# MCU_LF.net
KiCad netlist of a schematic drawn in Altium Designer
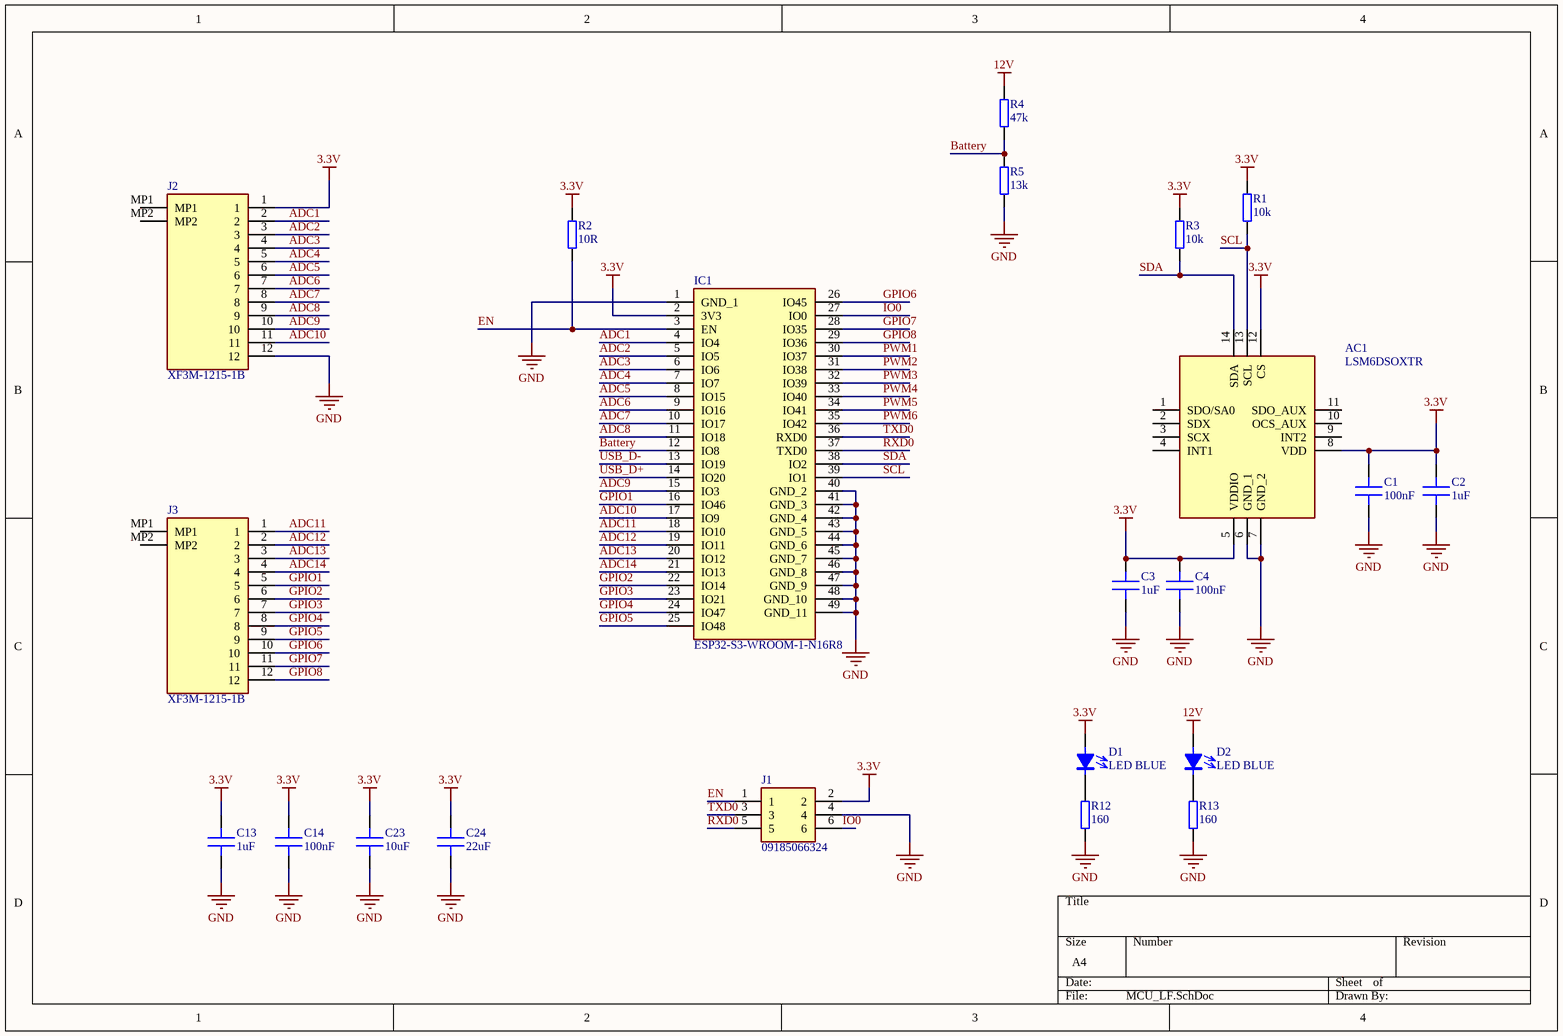
[diagram p0: MCU_LF.SchDoc]

(export (version "E")
  (design (tool "Eeschema 10.0.6"))
  (components
    (comp (ref "AC1")
      (value "LSM6DSOXTR")
      (footprint "SamacSys:LGA-14_1")
      (description "Accelerometer")
      (fields (field (name "MOUSER PART NUMBER") "511-LSM6DSOXTR"))
      (libsource (lib "lf_esp_sch_lib") (part "LSM6DSOXTR"))
    )
    (comp (ref "C1")
      (value "100nF")
      (footprint "C 0402")
      (description "MLCC Capacitor")
      (libsource (lib "Components") (part "Capacitor"))
    )
    (comp (ref "C2")
      (value "1uF")
      (footprint "C 0402")
      (description "MLCC Capacitor")
      (libsource (lib "Components") (part "Capacitor"))
    )
    (comp (ref "C3")
      (value "1uF")
      (footprint "C 0402")
      (description "MLCC Capacitor")
      (libsource (lib "Components") (part "Capacitor"))
    )
    (comp (ref "C4")
      (value "100nF")
      (footprint "C 0402")
      (description "MLCC Capacitor")
      (libsource (lib "Components") (part "Capacitor"))
    )
    (comp (ref "C13")
      (value "1uF")
      (footprint "C 0402")
      (description "MLCC Capacitor")
      (libsource (lib "Components") (part "Capacitor"))
    )
    (comp (ref "C14")
      (value "100nF")
      (footprint "C 0402")
      (description "MLCC Capacitor")
      (libsource (lib "Components") (part "Capacitor"))
    )
    (comp (ref "C23")
      (value "10uF")
      (footprint "C 0402")
      (description "MLCC Capacitor")
      (libsource (lib "Components") (part "Capacitor"))
    )
    (comp (ref "C24")
      (value "22uF")
      (footprint "C 0402")
      (description "MLCC Capacitor")
      (libsource (lib "Components") (part "Capacitor"))
    )
    (comp (ref "D1")
      (value "LED BLUE")
      (footprint "LED 0603 BLUE")
      (libsource (lib "Components") (part "LED BLUE"))
    )
    (comp (ref "D2")
      (value "LED BLUE")
      (footprint "LED 0603 BLUE")
      (libsource (lib "Components") (part "LED BLUE"))
    )
    (comp (ref "IC1")
      (value "ESP32-S3-WROOM-1-N16R8")
      (footprint "lf_esp_pcb_lib:ESP32S3WROOM1N16R8")
      (description "Integrated Circuit")
      (fields (field (name "MOUSER PART NUMBER") "356-ESP32S3WRM1N16R8"))
      (libsource (lib "lf_esp_sch_lib") (part "ESP32-S3-WROOM-1-N16R8"))
    )
    (comp (ref "J1")
      (value "09185066324")
      (footprint "SamacSys:09185066324")
      (description "Connector")
      (fields (field (name "MOUSER PART NUMBER") "617-09185066324"))
      (libsource (lib "lf_esp_sch_lib") (part "09185066324"))
    )
    (comp (ref "J2")
      (value "XF3M-1215-1B")
      (footprint "SamacSys:XF3M12151B")
      (description "Connector")
      (fields (field (name "MOUSER PART NUMBER") "653-XF3M-1215-1B"))
      (libsource (lib "lf_esp_sch_lib") (part "XF3M-1215-1B"))
    )
    (comp (ref "J3")
      (value "XF3M-1215-1B")
      (footprint "SamacSys:XF3M12151B")
      (description "Connector")
      (fields (field (name "MOUSER PART NUMBER") "653-XF3M-1215-1B"))
      (libsource (lib "lf_esp_sch_lib") (part "XF3M-1215-1B"))
    )
    (comp (ref "R1")
      (value "10k")
      (footprint "R 0402")
      (description "General pourpouse resistor")
      (libsource (lib "Components") (part "Resistor"))
    )
    (comp (ref "R2")
      (value "10R")
      (footprint "R 0402")
      (description "General pourpouse resistor")
      (libsource (lib "Components") (part "Resistor"))
    )
    (comp (ref "R3")
      (value "10k")
      (footprint "R 0402")
      (description "General pourpouse resistor")
      (libsource (lib "Components") (part "Resistor"))
    )
    (comp (ref "R4")
      (value "47k")
      (footprint "R 0402")
      (description "General pourpouse resistor")
      (libsource (lib "Components") (part "Resistor"))
    )
    (comp (ref "R5")
      (value "13k")
      (footprint "R 0402")
      (description "General pourpouse resistor")
      (libsource (lib "Components") (part "Resistor"))
    )
    (comp (ref "R12")
      (value "160")
      (footprint "R 0402")
      (description "General pourpouse resistor")
      (libsource (lib "Components") (part "Resistor"))
    )
    (comp (ref "R13")
      (value "160")
      (footprint "R 0402")
      (description "General pourpouse resistor")
      (libsource (lib "Components") (part "Resistor"))
    )
  )
  (nets
    (net (code "1") (name "/ADC1") (class "Default")
      (node (ref "IC1") (pin "4") (pinfunction "IO4_4") (pintype "passive"))
      (node (ref "J2") (pin "2") (pinfunction "2_2") (pintype "passive"))
    )
    (net (code "2") (name "/ADC2") (class "Default")
      (node (ref "IC1") (pin "5") (pinfunction "IO5_5") (pintype "passive"))
      (node (ref "J2") (pin "3") (pinfunction "3_3") (pintype "passive"))
    )
    (net (code "3") (name "/ADC3") (class "Default")
      (node (ref "IC1") (pin "6") (pinfunction "IO6_6") (pintype "passive"))
      (node (ref "J2") (pin "4") (pinfunction "4_4") (pintype "passive"))
    )
    (net (code "4") (name "/ADC4") (class "Default")
      (node (ref "IC1") (pin "7") (pinfunction "IO7_7") (pintype "passive"))
      (node (ref "J2") (pin "5") (pinfunction "5_5") (pintype "passive"))
    )
    (net (code "5") (name "/ADC5") (class "Default")
      (node (ref "IC1") (pin "8") (pinfunction "IO15_8") (pintype "passive"))
      (node (ref "J2") (pin "6") (pinfunction "6_6") (pintype "passive"))
    )
    (net (code "6") (name "/ADC6") (class "Default")
      (node (ref "IC1") (pin "9") (pinfunction "IO16_9") (pintype "passive"))
      (node (ref "J2") (pin "7") (pinfunction "7_7") (pintype "passive"))
    )
    (net (code "7") (name "/ADC7") (class "Default")
      (node (ref "IC1") (pin "10") (pinfunction "IO17_10") (pintype "passive"))
      (node (ref "J2") (pin "8") (pinfunction "8_8") (pintype "passive"))
    )
    (net (code "8") (name "/ADC8") (class "Default")
      (node (ref "IC1") (pin "11") (pinfunction "IO18_11") (pintype "passive"))
      (node (ref "J2") (pin "9") (pinfunction "9_9") (pintype "passive"))
    )
    (net (code "9") (name "/ADC9") (class "Default")
      (node (ref "IC1") (pin "15") (pinfunction "IO3_15") (pintype "passive"))
      (node (ref "J2") (pin "10") (pinfunction "10_10") (pintype "passive"))
    )
    (net (code "10") (name "/ADC10") (class "Default")
      (node (ref "IC1") (pin "17") (pinfunction "IO9_17") (pintype "passive"))
      (node (ref "J2") (pin "11") (pinfunction "11_11") (pintype "passive"))
    )
    (net (code "11") (name "/ADC11") (class "Default")
      (node (ref "IC1") (pin "18") (pinfunction "IO10_18") (pintype "passive"))
      (node (ref "J3") (pin "1") (pinfunction "1_1") (pintype "passive"))
    )
    (net (code "12") (name "/ADC12") (class "Default")
      (node (ref "IC1") (pin "19") (pinfunction "IO11_19") (pintype "passive"))
      (node (ref "J3") (pin "2") (pinfunction "2_2") (pintype "passive"))
    )
    (net (code "13") (name "/ADC13") (class "Default")
      (node (ref "IC1") (pin "20") (pinfunction "IO12_20") (pintype "passive"))
      (node (ref "J3") (pin "3") (pinfunction "3_3") (pintype "passive"))
    )
    (net (code "14") (name "/ADC14") (class "Default")
      (node (ref "IC1") (pin "21") (pinfunction "IO13_21") (pintype "passive"))
      (node (ref "J3") (pin "4") (pinfunction "4_4") (pintype "passive"))
    )
    (net (code "15") (name "/Battery") (class "Default")
      (node (ref "IC1") (pin "12") (pinfunction "IO8_12") (pintype "passive"))
      (node (ref "R4") (pin "1") (pinfunction "1_1") (pintype "passive"))
      (node (ref "R5") (pin "2") (pinfunction "2_2") (pintype "passive"))
    )
    (net (code "16") (name "/EN") (class "Default")
      (node (ref "IC1") (pin "3") (pinfunction "EN_3") (pintype "passive"))
      (node (ref "J1") (pin "1") (pinfunction "1_1") (pintype "passive"))
      (node (ref "R2") (pin "1") (pinfunction "1_1") (pintype "passive"))
    )
    (net (code "17") (name "/GPIO1") (class "Default")
      (node (ref "IC1") (pin "16") (pinfunction "IO46_16") (pintype "passive"))
      (node (ref "J3") (pin "5") (pinfunction "5_5") (pintype "passive"))
    )
    (net (code "18") (name "/GPIO2") (class "Default")
      (node (ref "IC1") (pin "22") (pinfunction "IO14_22") (pintype "passive"))
      (node (ref "J3") (pin "6") (pinfunction "6_6") (pintype "passive"))
    )
    (net (code "19") (name "/GPIO3") (class "Default")
      (node (ref "IC1") (pin "23") (pinfunction "IO21_23") (pintype "passive"))
      (node (ref "J3") (pin "7") (pinfunction "7_7") (pintype "passive"))
    )
    (net (code "20") (name "/GPIO4") (class "Default")
      (node (ref "IC1") (pin "24") (pinfunction "IO47_24") (pintype "passive"))
      (node (ref "J3") (pin "8") (pinfunction "8_8") (pintype "passive"))
    )
    (net (code "21") (name "/GPIO5") (class "Default")
      (node (ref "IC1") (pin "25") (pinfunction "IO48_25") (pintype "passive"))
      (node (ref "J3") (pin "9") (pinfunction "9_9") (pintype "passive"))
    )
    (net (code "22") (name "/GPIO6") (class "Default")
      (node (ref "IC1") (pin "26") (pinfunction "IO45_26") (pintype "passive"))
      (node (ref "J3") (pin "10") (pinfunction "10_10") (pintype "passive"))
    )
    (net (code "23") (name "/GPIO7") (class "Default")
      (node (ref "IC1") (pin "28") (pinfunction "IO35_28") (pintype "passive"))
      (node (ref "J3") (pin "11") (pinfunction "11_11") (pintype "passive"))
    )
    (net (code "24") (name "/GPIO8") (class "Default")
      (node (ref "IC1") (pin "29") (pinfunction "IO36_29") (pintype "passive"))
      (node (ref "J3") (pin "12") (pinfunction "12_12") (pintype "passive"))
    )
    (net (code "25") (name "/IO0") (class "Default")
      (node (ref "IC1") (pin "27") (pinfunction "IO0_27") (pintype "passive"))
      (node (ref "J1") (pin "6") (pinfunction "6_6") (pintype "passive"))
    )
    (net (code "26") (name "/PWM1") (class "Default")
      (node (ref "IC1") (pin "30") (pinfunction "IO37_30") (pintype "passive"))
    )
    (net (code "27") (name "/PWM2") (class "Default")
      (node (ref "IC1") (pin "31") (pinfunction "IO38_31") (pintype "passive"))
    )
    (net (code "28") (name "/PWM3") (class "Default")
      (node (ref "IC1") (pin "32") (pinfunction "IO39_32") (pintype "passive"))
    )
    (net (code "29") (name "/PWM4") (class "Default")
      (node (ref "IC1") (pin "33") (pinfunction "IO40_33") (pintype "passive"))
    )
    (net (code "30") (name "/PWM5") (class "Default")
      (node (ref "IC1") (pin "34") (pinfunction "IO41_34") (pintype "passive"))
    )
    (net (code "31") (name "/PWM6") (class "Default")
      (node (ref "IC1") (pin "35") (pinfunction "IO42_35") (pintype "passive"))
    )
    (net (code "32") (name "/RXD0") (class "Default")
      (node (ref "IC1") (pin "37") (pinfunction "TXD0_37") (pintype "passive"))
      (node (ref "J1") (pin "5") (pinfunction "5_5") (pintype "passive"))
    )
    (net (code "33") (name "/SCL") (class "Default")
      (node (ref "AC1") (pin "13") (pinfunction "SCL_13") (pintype "passive"))
      (node (ref "IC1") (pin "39") (pinfunction "IO1_39") (pintype "passive"))
      (node (ref "R1") (pin "1") (pinfunction "1_1") (pintype "passive"))
    )
    (net (code "34") (name "/SDA") (class "Default")
      (node (ref "AC1") (pin "14") (pinfunction "SDA_14") (pintype "passive"))
      (node (ref "IC1") (pin "38") (pinfunction "IO2_38") (pintype "passive"))
      (node (ref "R3") (pin "1") (pinfunction "1_1") (pintype "passive"))
    )
    (net (code "35") (name "/TXD0") (class "Default")
      (node (ref "IC1") (pin "36") (pinfunction "RXD0_36") (pintype "passive"))
      (node (ref "J1") (pin "3") (pinfunction "3_3") (pintype "passive"))
    )
    (net (code "36") (name "/USB_D+") (class "Default")
      (node (ref "IC1") (pin "14") (pinfunction "IO20_14") (pintype "passive"))
    )
    (net (code "37") (name "/USB_D-") (class "Default")
      (node (ref "IC1") (pin "13") (pinfunction "IO19_13") (pintype "passive"))
    )
    (net (code "38") (name "3.3V") (class "Default")
      (node (ref "AC1") (pin "12") (pinfunction "CS_12") (pintype "passive"))
      (node (ref "AC1") (pin "5") (pinfunction "VDDIO_5") (pintype "passive"))
      (node (ref "AC1") (pin "8") (pinfunction "VDD_8") (pintype "passive"))
      (node (ref "C1") (pin "1") (pinfunction "1_1") (pintype "passive"))
      (node (ref "C13") (pin "1") (pinfunction "1_1") (pintype "passive"))
      (node (ref "C14") (pin "1") (pinfunction "1_1") (pintype "passive"))
      (node (ref "C2") (pin "1") (pinfunction "1_1") (pintype "passive"))
      (node (ref "C23") (pin "1") (pinfunction "1_1") (pintype "passive"))
      (node (ref "C24") (pin "1") (pinfunction "1_1") (pintype "passive"))
      (node (ref "C3") (pin "1") (pinfunction "1_1") (pintype "passive"))
      (node (ref "C4") (pin "1") (pinfunction "1_1") (pintype "passive"))
      (node (ref "D1") (pin "1") (pinfunction "1_1") (pintype "passive"))
      (node (ref "IC1") (pin "2") (pinfunction "3V3_2") (pintype "passive"))
      (node (ref "J1") (pin "2") (pinfunction "2_2") (pintype "passive"))
      (node (ref "J2") (pin "1") (pinfunction "1_1") (pintype "passive"))
      (node (ref "R1") (pin "2") (pinfunction "2_2") (pintype "passive"))
      (node (ref "R2") (pin "2") (pinfunction "2_2") (pintype "passive"))
      (node (ref "R3") (pin "2") (pinfunction "2_2") (pintype "passive"))
    )
    (net (code "39") (name "12V") (class "Default")
      (node (ref "D2") (pin "1") (pinfunction "1_1") (pintype "passive"))
      (node (ref "R4") (pin "2") (pinfunction "2_2") (pintype "passive"))
    )
    (net (code "40") (name "GND") (class "Default")
      (node (ref "AC1") (pin "6") (pinfunction "GND_1_6") (pintype "passive"))
      (node (ref "AC1") (pin "7") (pinfunction "GND_2_7") (pintype "passive"))
      (node (ref "C1") (pin "2") (pinfunction "2_2") (pintype "passive"))
      (node (ref "C13") (pin "2") (pinfunction "2_2") (pintype "passive"))
      (node (ref "C14") (pin "2") (pinfunction "2_2") (pintype "passive"))
      (node (ref "C2") (pin "2") (pinfunction "2_2") (pintype "passive"))
      (node (ref "C23") (pin "2") (pinfunction "2_2") (pintype "passive"))
      (node (ref "C24") (pin "2") (pinfunction "2_2") (pintype "passive"))
      (node (ref "C3") (pin "2") (pinfunction "2_2") (pintype "passive"))
      (node (ref "C4") (pin "2") (pinfunction "2_2") (pintype "passive"))
      (node (ref "IC1") (pin "1") (pinfunction "GND_1_1") (pintype "passive"))
      (node (ref "IC1") (pin "40") (pinfunction "GND_2_40") (pintype "passive"))
      (node (ref "IC1") (pin "41") (pinfunction "GND_3_41") (pintype "passive"))
      (node (ref "IC1") (pin "42") (pinfunction "GND_4_42") (pintype "passive"))
      (node (ref "IC1") (pin "43") (pinfunction "GND_5_43") (pintype "passive"))
      (node (ref "IC1") (pin "44") (pinfunction "GND_6_44") (pintype "passive"))
      (node (ref "IC1") (pin "45") (pinfunction "GND_7_45") (pintype "passive"))
      (node (ref "IC1") (pin "46") (pinfunction "GND_8_46") (pintype "passive"))
      (node (ref "IC1") (pin "47") (pinfunction "GND_9_47") (pintype "passive"))
      (node (ref "IC1") (pin "48") (pinfunction "GND_10_48") (pintype "passive"))
      (node (ref "IC1") (pin "49") (pinfunction "GND_11_49") (pintype "passive"))
      (node (ref "J1") (pin "4") (pinfunction "4_4") (pintype "passive"))
      (node (ref "J2") (pin "12") (pinfunction "12_12") (pintype "passive"))
      (node (ref "R12") (pin "1") (pinfunction "1_1") (pintype "passive"))
      (node (ref "R13") (pin "1") (pinfunction "1_1") (pintype "passive"))
      (node (ref "R5") (pin "1") (pinfunction "1_1") (pintype "passive"))
    )
    (net (code "41") (name "Net-(D1-Pad2)") (class "Default")
      (node (ref "D1") (pin "2") (pinfunction "2_2") (pintype "passive"))
      (node (ref "R12") (pin "2") (pinfunction "2_2") (pintype "passive"))
    )
    (net (code "42") (name "Net-(D2-Pad2)") (class "Default")
      (node (ref "D2") (pin "2") (pinfunction "2_2") (pintype "passive"))
      (node (ref "R13") (pin "2") (pinfunction "2_2") (pintype "passive"))
    )
    (net (code "43") (name "unconnected-(AC1-INT1-Pad4)") (class "Default")
      (node (ref "AC1") (pin "4") (pinfunction "INT1_4") (pintype "passive"))
    )
    (net (code "44") (name "unconnected-(AC1-INT2-Pad9)") (class "Default")
      (node (ref "AC1") (pin "9") (pinfunction "INT2_9") (pintype "passive"))
    )
    (net (code "45") (name "unconnected-(AC1-OCS_AUX-Pad10)") (class "Default")
      (node (ref "AC1") (pin "10") (pinfunction "OCS_AUX_10") (pintype "passive"))
    )
    (net (code "46") (name "unconnected-(AC1-SCX-Pad3)") (class "Default")
      (node (ref "AC1") (pin "3") (pinfunction "SCX_3") (pintype "passive"))
    )
    (net (code "47") (name "unconnected-(AC1-SDO_AUX-Pad11)") (class "Default")
      (node (ref "AC1") (pin "11") (pinfunction "SDO_AUX_11") (pintype "passive"))
    )
    (net (code "48") (name "unconnected-(AC1-SDO{slash}SA0-Pad1)") (class "Default")
      (node (ref "AC1") (pin "1") (pinfunction "SDO/SA0_1") (pintype "passive"))
    )
    (net (code "49") (name "unconnected-(AC1-SDX-Pad2)") (class "Default")
      (node (ref "AC1") (pin "2") (pinfunction "SDX_2") (pintype "passive"))
    )
    (net (code "50") (name "unconnected-(J2-PadMP1)") (class "Default")
      (node (ref "J2") (pin "MP1") (pinfunction "MP1_MP1") (pintype "passive"))
    )
    (net (code "51") (name "unconnected-(J2-PadMP2)") (class "Default")
      (node (ref "J2") (pin "MP2") (pinfunction "MP2_MP2") (pintype "passive"))
    )
    (net (code "52") (name "unconnected-(J3-PadMP1)") (class "Default")
      (node (ref "J3") (pin "MP1") (pinfunction "MP1_MP1") (pintype "passive"))
    )
    (net (code "53") (name "unconnected-(J3-PadMP2)") (class "Default")
      (node (ref "J3") (pin "MP2") (pinfunction "MP2_MP2") (pintype "passive"))
    )
  )
)
